# LTC6803.net
KiCad netlist of a schematic drawn in Altium Designer
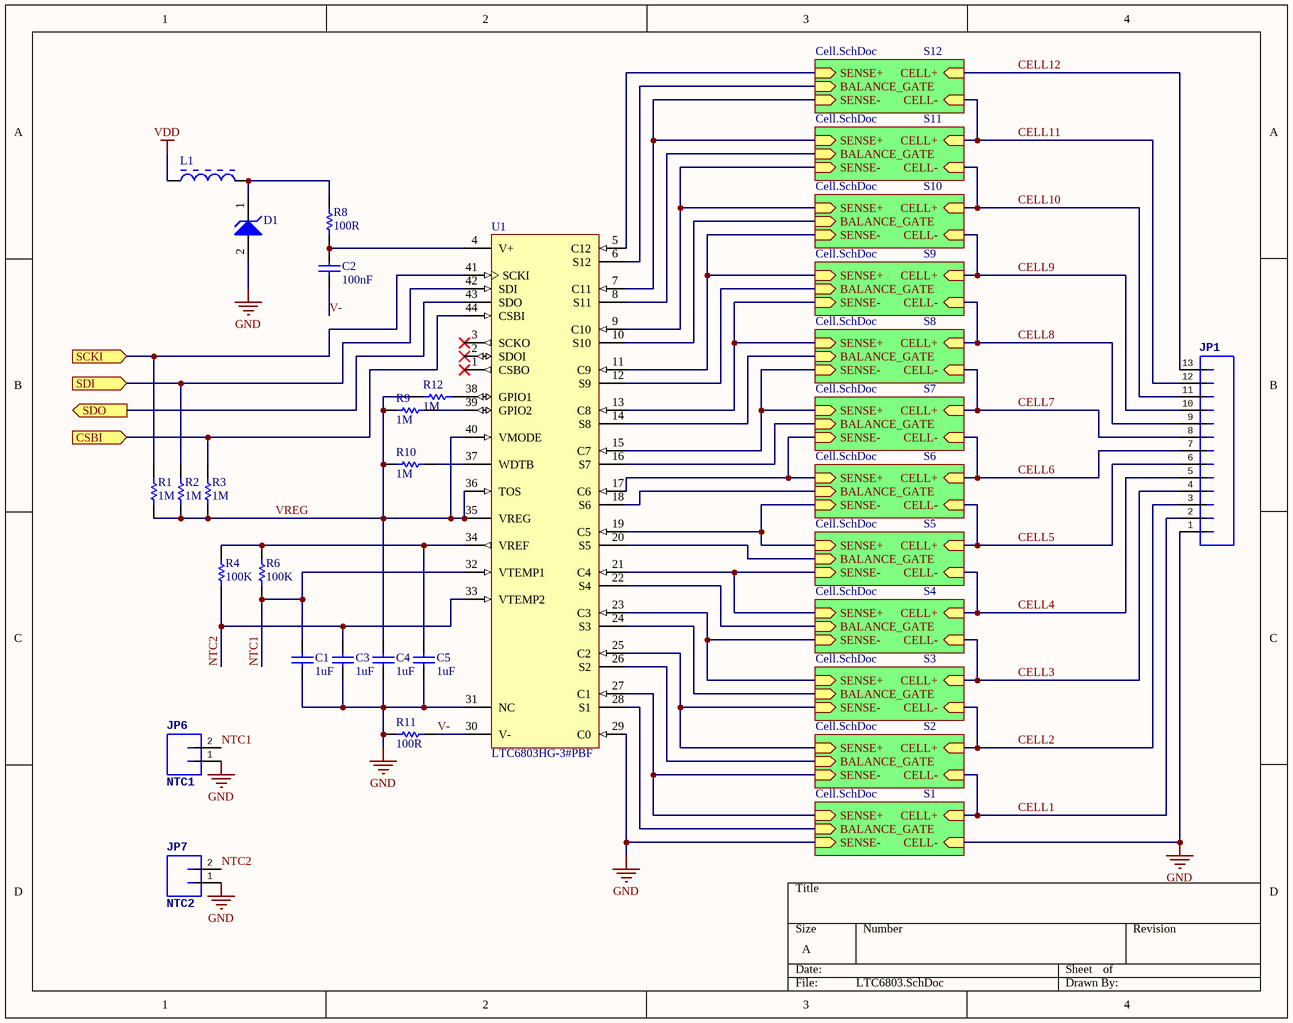
[diagram p0: LTC6803.SchDoc]

(export (version "E")
  (design (tool "Eeschema 10.0.6"))
  (components
    (comp (ref "C1")
      (value "1uF")
      (footprint "CAPC0603(1608)100_N")
      (description "CAP 1uF 6.3V Â±10% 0603 (1608 Metric) Thickness 1mm SMD")
      (fields (field (name "TOLERANCE") "Â±10%"))
      (libsource (lib "Altium Content Vault") (part "CAP"))
    )
    (comp (ref "C2")
      (value "100nF")
      (footprint "CAPC0603(1608)100_L")
      (description "CAP 100nF 100V Â±10% 0603 (1608 Metric) Thickness 1mm SMD")
      (fields (field (name "TOLERANCE") "Â±10%"))
      (libsource (lib "Altium Content Vault") (part "CAP"))
    )
    (comp (ref "C3")
      (value "1uF")
      (footprint "CAPC0603(1608)100_N")
      (description "CAP 1uF 6.3V Â±10% 0603 (1608 Metric) Thickness 1mm SMD")
      (fields (field (name "TOLERANCE") "Â±10%"))
      (libsource (lib "Altium Content Vault") (part "CAP"))
    )
    (comp (ref "C4")
      (value "1uF")
      (footprint "CAPC0603(1608)100_N")
      (description "CAP 1uF 6.3V Â±10% 0603 (1608 Metric) Thickness 1mm SMD")
      (fields (field (name "TOLERANCE") "Â±10%"))
      (libsource (lib "Altium Content Vault") (part "CAP"))
    )
    (comp (ref "C5")
      (value "1uF")
      (footprint "CAPC0603(1608)100_N")
      (description "CAP 1uF 6.3V Â±10% 0603 (1608 Metric) Thickness 1mm SMD")
      (fields (field (name "TOLERANCE") "Â±10%"))
      (libsource (lib "Altium Content Vault") (part "CAP"))
    )
    (comp (ref "D1") (value "~") (footprint "SOD-123") (libsource (lib "Components") (part "CMHZ5265B")))
    (comp (ref "JP1")
      (value "~")
      (footprint "JST-13-PTH-VERT")
      (libsource (lib "Components") (part "JST_XH_13"))
    )
    (comp (ref "JP6")
      (value "NTC1")
      (footprint "JST-2-PTH-VERT")
      (libsource (lib "Components") (part "JST_2_VERT"))
    )
    (comp (ref "JP7")
      (value "NTC2")
      (footprint "JST-2-PTH-VERT")
      (libsource (lib "Components") (part "JST_2_VERT"))
    )
    (comp (ref "L1")
      (value "~")
      (footprint "MURA-BLM31-B60-CHIP-2_V3")
      (libsource (lib "Components") (part "MURA-FB-2"))
    )
    (comp (ref "R1")
      (value "1M")
      (footprint "RESC0603(1608)_L")
      (description "1M 0.1W 1% 0603 (1608 Metric)  SMD")
      (fields (field (name "POWER") "0.1 W") (field (name "TOLERANCE") "1 %"))
      (libsource (lib "Altium Content Vault") (part "RES"))
    )
    (comp (ref "R2")
      (value "1M")
      (footprint "RESC0603(1608)_L")
      (description "1M 0.1W 1% 0603 (1608 Metric)  SMD")
      (fields (field (name "POWER") "0.1 W") (field (name "TOLERANCE") "1 %"))
      (libsource (lib "Altium Content Vault") (part "RES"))
    )
    (comp (ref "R3")
      (value "1M")
      (footprint "RESC0603(1608)_L")
      (description "1M 0.1W 1% 0603 (1608 Metric)  SMD")
      (fields (field (name "POWER") "0.1 W") (field (name "TOLERANCE") "1 %"))
      (libsource (lib "Altium Content Vault") (part "RES"))
    )
    (comp (ref "R4")
      (value "100K")
      (footprint "RESC0603(1608)_N")
      (description "100K 0.1W 5% 0603 (1608 Metric)  SMD")
      (fields (field (name "TOLERANCE") "5 %") (field (name "POWER") "0.1 W"))
      (libsource (lib "Altium Content Vault") (part "RES"))
    )
    (comp (ref "R6")
      (value "100K")
      (footprint "RESC0603(1608)_N")
      (description "100K 0.1W 5% 0603 (1608 Metric)  SMD")
      (fields (field (name "TOLERANCE") "5 %") (field (name "POWER") "0.1 W"))
      (libsource (lib "Altium Content Vault") (part "RES"))
    )
    (comp (ref "R8")
      (value "100R")
      (footprint "RESC0603(1608)_L")
      (description "100R 0.1W 5% 0603 (1608 Metric)  SMD")
      (fields (field (name "TOLERANCE") "5 %") (field (name "POWER") "0.1 W"))
      (libsource (lib "Altium Content Vault") (part "CMP-1012-00050-1"))
    )
    (comp (ref "R9")
      (value "1M")
      (footprint "RESC0603(1608)_L")
      (description "1M 0.1W 1% 0603 (1608 Metric)  SMD")
      (fields (field (name "POWER") "0.1 W") (field (name "TOLERANCE") "1 %"))
      (libsource (lib "Altium Content Vault") (part "RES"))
    )
    (comp (ref "R10")
      (value "1M")
      (footprint "RESC0603(1608)_L")
      (description "1M 0.1W 1% 0603 (1608 Metric)  SMD")
      (fields (field (name "POWER") "0.1 W") (field (name "TOLERANCE") "1 %"))
      (libsource (lib "Altium Content Vault") (part "RES"))
    )
    (comp (ref "R11")
      (value "100R")
      (footprint "RESC0603(1608)_L")
      (description "100R 0.1W 5% 0603 (1608 Metric)  SMD")
      (fields (field (name "TOLERANCE") "5 %") (field (name "POWER") "0.1 W"))
      (libsource (lib "Altium Content Vault") (part "RES"))
    )
    (comp (ref "R12")
      (value "1M")
      (footprint "RESC0603(1608)_L")
      (description "1M 0.1W 1% 0603 (1608 Metric)  SMD")
      (fields (field (name "POWER") "0.1 W") (field (name "TOLERANCE") "1 %"))
      (libsource (lib "Altium Content Vault") (part "RES"))
    )
    (comp (ref "U1")
      (value "LTC6803HG-3#PBF")
      (footprint "LT-G-44_L")
      (description "Multicell Battery Stack Monitor, 60 V Vin MAX, 44-pin SOP (G-44), -40 to 125 degC, Pb-Free")
      (fields (field (name "MANUFACTURER") "Linear Technology"))
      (libsource (lib "Altium Content Vault") (part "LT-LTC6803-3-G-44"))
    )
  )
  (nets
    (net (code "1") (name "/BALANCE_GATE") (class "Default")
      (node (ref "U1") (pin "16") (pinfunction "S7_16") (pintype "tri_state"))
    )
    (net (code "2") (name "/BALANCE_GATE_1") (class "Default")
      (node (ref "U1") (pin "8") (pinfunction "S11_8") (pintype "tri_state"))
    )
    (net (code "3") (name "/BALANCE_GATE_2") (class "Default")
      (node (ref "U1") (pin "18") (pinfunction "S6_18") (pintype "tri_state"))
    )
    (net (code "4") (name "/BALANCE_GATE_3") (class "Default")
      (node (ref "U1") (pin "6") (pinfunction "S12_6") (pintype "tri_state"))
    )
    (net (code "5") (name "/BALANCE_GATE_4") (class "Default")
      (node (ref "U1") (pin "28") (pinfunction "S1_28") (pintype "tri_state"))
    )
    (net (code "6") (name "/BALANCE_GATE_5") (class "Default")
      (node (ref "U1") (pin "20") (pinfunction "S5_20") (pintype "tri_state"))
    )
    (net (code "7") (name "/BALANCE_GATE_6") (class "Default")
      (node (ref "U1") (pin "22") (pinfunction "S4_22") (pintype "tri_state"))
    )
    (net (code "8") (name "/BALANCE_GATE_7") (class "Default")
      (node (ref "U1") (pin "26") (pinfunction "S2_26") (pintype "tri_state"))
    )
    (net (code "9") (name "/BALANCE_GATE_8") (class "Default")
      (node (ref "U1") (pin "24") (pinfunction "S3_24") (pintype "tri_state"))
    )
    (net (code "10") (name "/BALANCE_GATE_9") (class "Default")
      (node (ref "U1") (pin "10") (pinfunction "S10_10") (pintype "tri_state"))
    )
    (net (code "11") (name "/BALANCE_GATE_10") (class "Default")
      (node (ref "U1") (pin "12") (pinfunction "S9_12") (pintype "tri_state"))
    )
    (net (code "12") (name "/BALANCE_GATE_11") (class "Default")
      (node (ref "U1") (pin "14") (pinfunction "S8_14") (pintype "tri_state"))
    )
    (net (code "13") (name "/CELL1") (class "Default")
      (node (ref "JP1") (pin "2") (pinfunction "2_2") (pintype "passive"))
    )
    (net (code "14") (name "/CELL2") (class "Default")
      (node (ref "JP1") (pin "3") (pinfunction "3_3") (pintype "passive"))
    )
    (net (code "15") (name "/CELL3") (class "Default")
      (node (ref "JP1") (pin "4") (pinfunction "4_4") (pintype "passive"))
    )
    (net (code "16") (name "/CELL4") (class "Default")
      (node (ref "JP1") (pin "5") (pinfunction "5_5") (pintype "passive"))
    )
    (net (code "17") (name "/CELL5") (class "Default")
      (node (ref "JP1") (pin "6") (pinfunction "6_6") (pintype "passive"))
    )
    (net (code "18") (name "/CELL6") (class "Default")
      (node (ref "JP1") (pin "7") (pinfunction "7_7") (pintype "passive"))
    )
    (net (code "19") (name "/CELL7") (class "Default")
      (node (ref "JP1") (pin "8") (pinfunction "8_8") (pintype "passive"))
    )
    (net (code "20") (name "/CELL8") (class "Default")
      (node (ref "JP1") (pin "9") (pinfunction "9_9") (pintype "passive"))
    )
    (net (code "21") (name "/CELL9") (class "Default")
      (node (ref "JP1") (pin "10") (pinfunction "10_10") (pintype "passive"))
    )
    (net (code "22") (name "/CELL10") (class "Default")
      (node (ref "JP1") (pin "11") (pinfunction "11_11") (pintype "passive"))
    )
    (net (code "23") (name "/CELL11") (class "Default")
      (node (ref "JP1") (pin "12") (pinfunction "12_12") (pintype "passive"))
    )
    (net (code "24") (name "/CELL12") (class "Default")
      (node (ref "JP1") (pin "13") (pinfunction "13_13") (pintype "passive"))
    )
    (net (code "25") (name "/CSBI") (class "Default")
      (node (ref "R3") (pin "2") (pinfunction "2_2") (pintype "passive"))
      (node (ref "U1") (pin "44") (pinfunction "CSBI_44") (pintype "input"))
    )
    (net (code "26") (name "/NTC1") (class "Default")
      (node (ref "C1") (pin "2") (pinfunction "2_2") (pintype "passive"))
      (node (ref "JP6") (pin "2") (pinfunction "2_2") (pintype "passive"))
      (node (ref "R6") (pin "1") (pinfunction "1_1") (pintype "passive"))
      (node (ref "U1") (pin "32") (pinfunction "VTEMP1_32") (pintype "input"))
    )
    (net (code "27") (name "/NTC2") (class "Default")
      (node (ref "C3") (pin "2") (pinfunction "2_2") (pintype "passive"))
      (node (ref "JP7") (pin "2") (pinfunction "2_2") (pintype "passive"))
      (node (ref "R4") (pin "1") (pinfunction "1_1") (pintype "passive"))
      (node (ref "U1") (pin "33") (pinfunction "VTEMP2_33") (pintype "input"))
    )
    (net (code "28") (name "/SCKI") (class "Default")
      (node (ref "R1") (pin "2") (pinfunction "2_2") (pintype "passive"))
      (node (ref "U1") (pin "41") (pinfunction "SCKI_41") (pintype "input"))
    )
    (net (code "29") (name "/SDI") (class "Default")
      (node (ref "R2") (pin "2") (pinfunction "2_2") (pintype "passive"))
      (node (ref "U1") (pin "42") (pinfunction "SDI_42") (pintype "input"))
    )
    (net (code "30") (name "/SDO") (class "Default")
      (node (ref "U1") (pin "43") (pinfunction "SDO_43") (pintype "open_collector"))
    )
    (net (code "31") (name "/SENSE+") (class "Default")
      (node (ref "U1") (pin "15") (pinfunction "C7_15") (pintype "input"))
    )
    (net (code "32") (name "/SENSE+_1") (class "Default")
      (node (ref "U1") (pin "9") (pinfunction "C10_9") (pintype "input"))
    )
    (net (code "33") (name "/SENSE+_2") (class "Default")
      (node (ref "U1") (pin "17") (pinfunction "C6_17") (pintype "input"))
    )
    (net (code "34") (name "/SENSE+_3") (class "Default")
      (node (ref "U1") (pin "7") (pinfunction "C11_7") (pintype "input"))
    )
    (net (code "35") (name "/SENSE+_4") (class "Default")
      (node (ref "U1") (pin "5") (pinfunction "C12_5") (pintype "input"))
    )
    (net (code "36") (name "/SENSE+_5") (class "Default")
      (node (ref "U1") (pin "19") (pinfunction "C5_19") (pintype "input"))
    )
    (net (code "37") (name "/SENSE+_6") (class "Default")
      (node (ref "U1") (pin "21") (pinfunction "C4_21") (pintype "input"))
    )
    (net (code "38") (name "/SENSE+_7") (class "Default")
      (node (ref "U1") (pin "23") (pinfunction "C3_23") (pintype "input"))
    )
    (net (code "39") (name "/SENSE+_8") (class "Default")
      (node (ref "U1") (pin "25") (pinfunction "C2_25") (pintype "input"))
    )
    (net (code "40") (name "/SENSE+_9") (class "Default")
      (node (ref "U1") (pin "27") (pinfunction "C1_27") (pintype "input"))
    )
    (net (code "41") (name "/SENSE+_10") (class "Default")
      (node (ref "U1") (pin "11") (pinfunction "C9_11") (pintype "input"))
    )
    (net (code "42") (name "/SENSE+_11") (class "Default")
      (node (ref "U1") (pin "13") (pinfunction "C8_13") (pintype "input"))
    )
    (net (code "43") (name "/V-") (class "Default")
      (node (ref "C2") (pin "1") (pinfunction "1_1") (pintype "passive"))
      (node (ref "R11") (pin "2") (pinfunction "2_2") (pintype "passive"))
      (node (ref "U1") (pin "30") (pinfunction "V-_30") (pintype "power_in"))
    )
    (net (code "44") (name "/VREG") (class "Default")
      (node (ref "C4") (pin "2") (pinfunction "2_2") (pintype "passive"))
      (node (ref "R1") (pin "1") (pinfunction "1_1") (pintype "passive"))
      (node (ref "R10") (pin "1") (pinfunction "1_1") (pintype "passive"))
      (node (ref "R12") (pin "1") (pinfunction "1_1") (pintype "passive"))
      (node (ref "R2") (pin "1") (pinfunction "1_1") (pintype "passive"))
      (node (ref "R3") (pin "1") (pinfunction "1_1") (pintype "passive"))
      (node (ref "R9") (pin "1") (pinfunction "1_1") (pintype "passive"))
      (node (ref "U1") (pin "35") (pinfunction "VREG_35") (pintype "power_in"))
      (node (ref "U1") (pin "36") (pinfunction "TOS_36") (pintype "input"))
      (node (ref "U1") (pin "40") (pinfunction "VMODE_40") (pintype "input"))
    )
    (net (code "45") (name "GND") (class "Default")
      (node (ref "C1") (pin "1") (pinfunction "1_1") (pintype "passive"))
      (node (ref "C3") (pin "1") (pinfunction "1_1") (pintype "passive"))
      (node (ref "C4") (pin "1") (pinfunction "1_1") (pintype "passive"))
      (node (ref "C5") (pin "1") (pinfunction "1_1") (pintype "passive"))
      (node (ref "D1") (pin "2") (pinfunction "A_2") (pintype "passive"))
      (node (ref "JP1") (pin "1") (pinfunction "1_1") (pintype "passive"))
      (node (ref "JP6") (pin "1") (pinfunction "1_1") (pintype "passive"))
      (node (ref "JP7") (pin "1") (pinfunction "1_1") (pintype "passive"))
      (node (ref "R11") (pin "1") (pinfunction "1_1") (pintype "passive"))
      (node (ref "U1") (pin "29") (pinfunction "C0_29") (pintype "input"))
      (node (ref "U1") (pin "31") (pinfunction "NC_31") (pintype "passive"))
    )
    (net (code "46") (name "Net-(D1-K)") (class "Default")
      (node (ref "D1") (pin "1") (pinfunction "K_1") (pintype "passive"))
      (node (ref "L1") (pin "2") (pinfunction "2_2") (pintype "passive"))
      (node (ref "R8") (pin "2") (pinfunction "2_2") (pintype "passive"))
    )
    (net (code "47") (name "Net-(U1-GPIO1)") (class "Default")
      (node (ref "R12") (pin "2") (pinfunction "2_2") (pintype "passive"))
      (node (ref "U1") (pin "38") (pinfunction "GPIO1_38") (pintype "bidirectional"))
    )
    (net (code "48") (name "Net-(U1-GPIO2)") (class "Default")
      (node (ref "R9") (pin "2") (pinfunction "2_2") (pintype "passive"))
      (node (ref "U1") (pin "39") (pinfunction "GPIO2_39") (pintype "bidirectional"))
    )
    (net (code "49") (name "Net-(U1-V+)") (class "Default")
      (node (ref "C2") (pin "2") (pinfunction "2_2") (pintype "passive"))
      (node (ref "R8") (pin "1") (pinfunction "1_1") (pintype "passive"))
      (node (ref "U1") (pin "4") (pinfunction "V+_4") (pintype "power_in"))
    )
    (net (code "50") (name "Net-(U1-VREF)") (class "Default")
      (node (ref "C5") (pin "2") (pinfunction "2_2") (pintype "passive"))
      (node (ref "R4") (pin "2") (pinfunction "2_2") (pintype "passive"))
      (node (ref "R6") (pin "2") (pinfunction "2_2") (pintype "passive"))
      (node (ref "U1") (pin "34") (pinfunction "VREF_34") (pintype "output"))
    )
    (net (code "51") (name "Net-(U1-WDTB)") (class "Default")
      (node (ref "R10") (pin "2") (pinfunction "2_2") (pintype "passive"))
      (node (ref "U1") (pin "37") (pinfunction "WDTB_37") (pintype "open_collector"))
    )
    (net (code "52") (name "VDD") (class "Default")
      (node (ref "L1") (pin "1") (pinfunction "1_1") (pintype "passive"))
    )
    (net (code "53") (name "unconnected-(U1-CSBO-Pad1)") (class "Default")
      (node (ref "U1") (pin "1") (pinfunction "CSBO_1") (pintype "output+no_connect"))
    )
    (net (code "54") (name "unconnected-(U1-SCKO-Pad3)") (class "Default")
      (node (ref "U1") (pin "3") (pinfunction "SCKO_3") (pintype "output+no_connect"))
    )
    (net (code "55") (name "unconnected-(U1-SDOI-Pad2)") (class "Default")
      (node (ref "U1") (pin "2") (pinfunction "SDOI_2") (pintype "bidirectional+no_connect"))
    )
  )
)
